# Feedback.net
KiCad netlist of a schematic drawn in Altium Designer
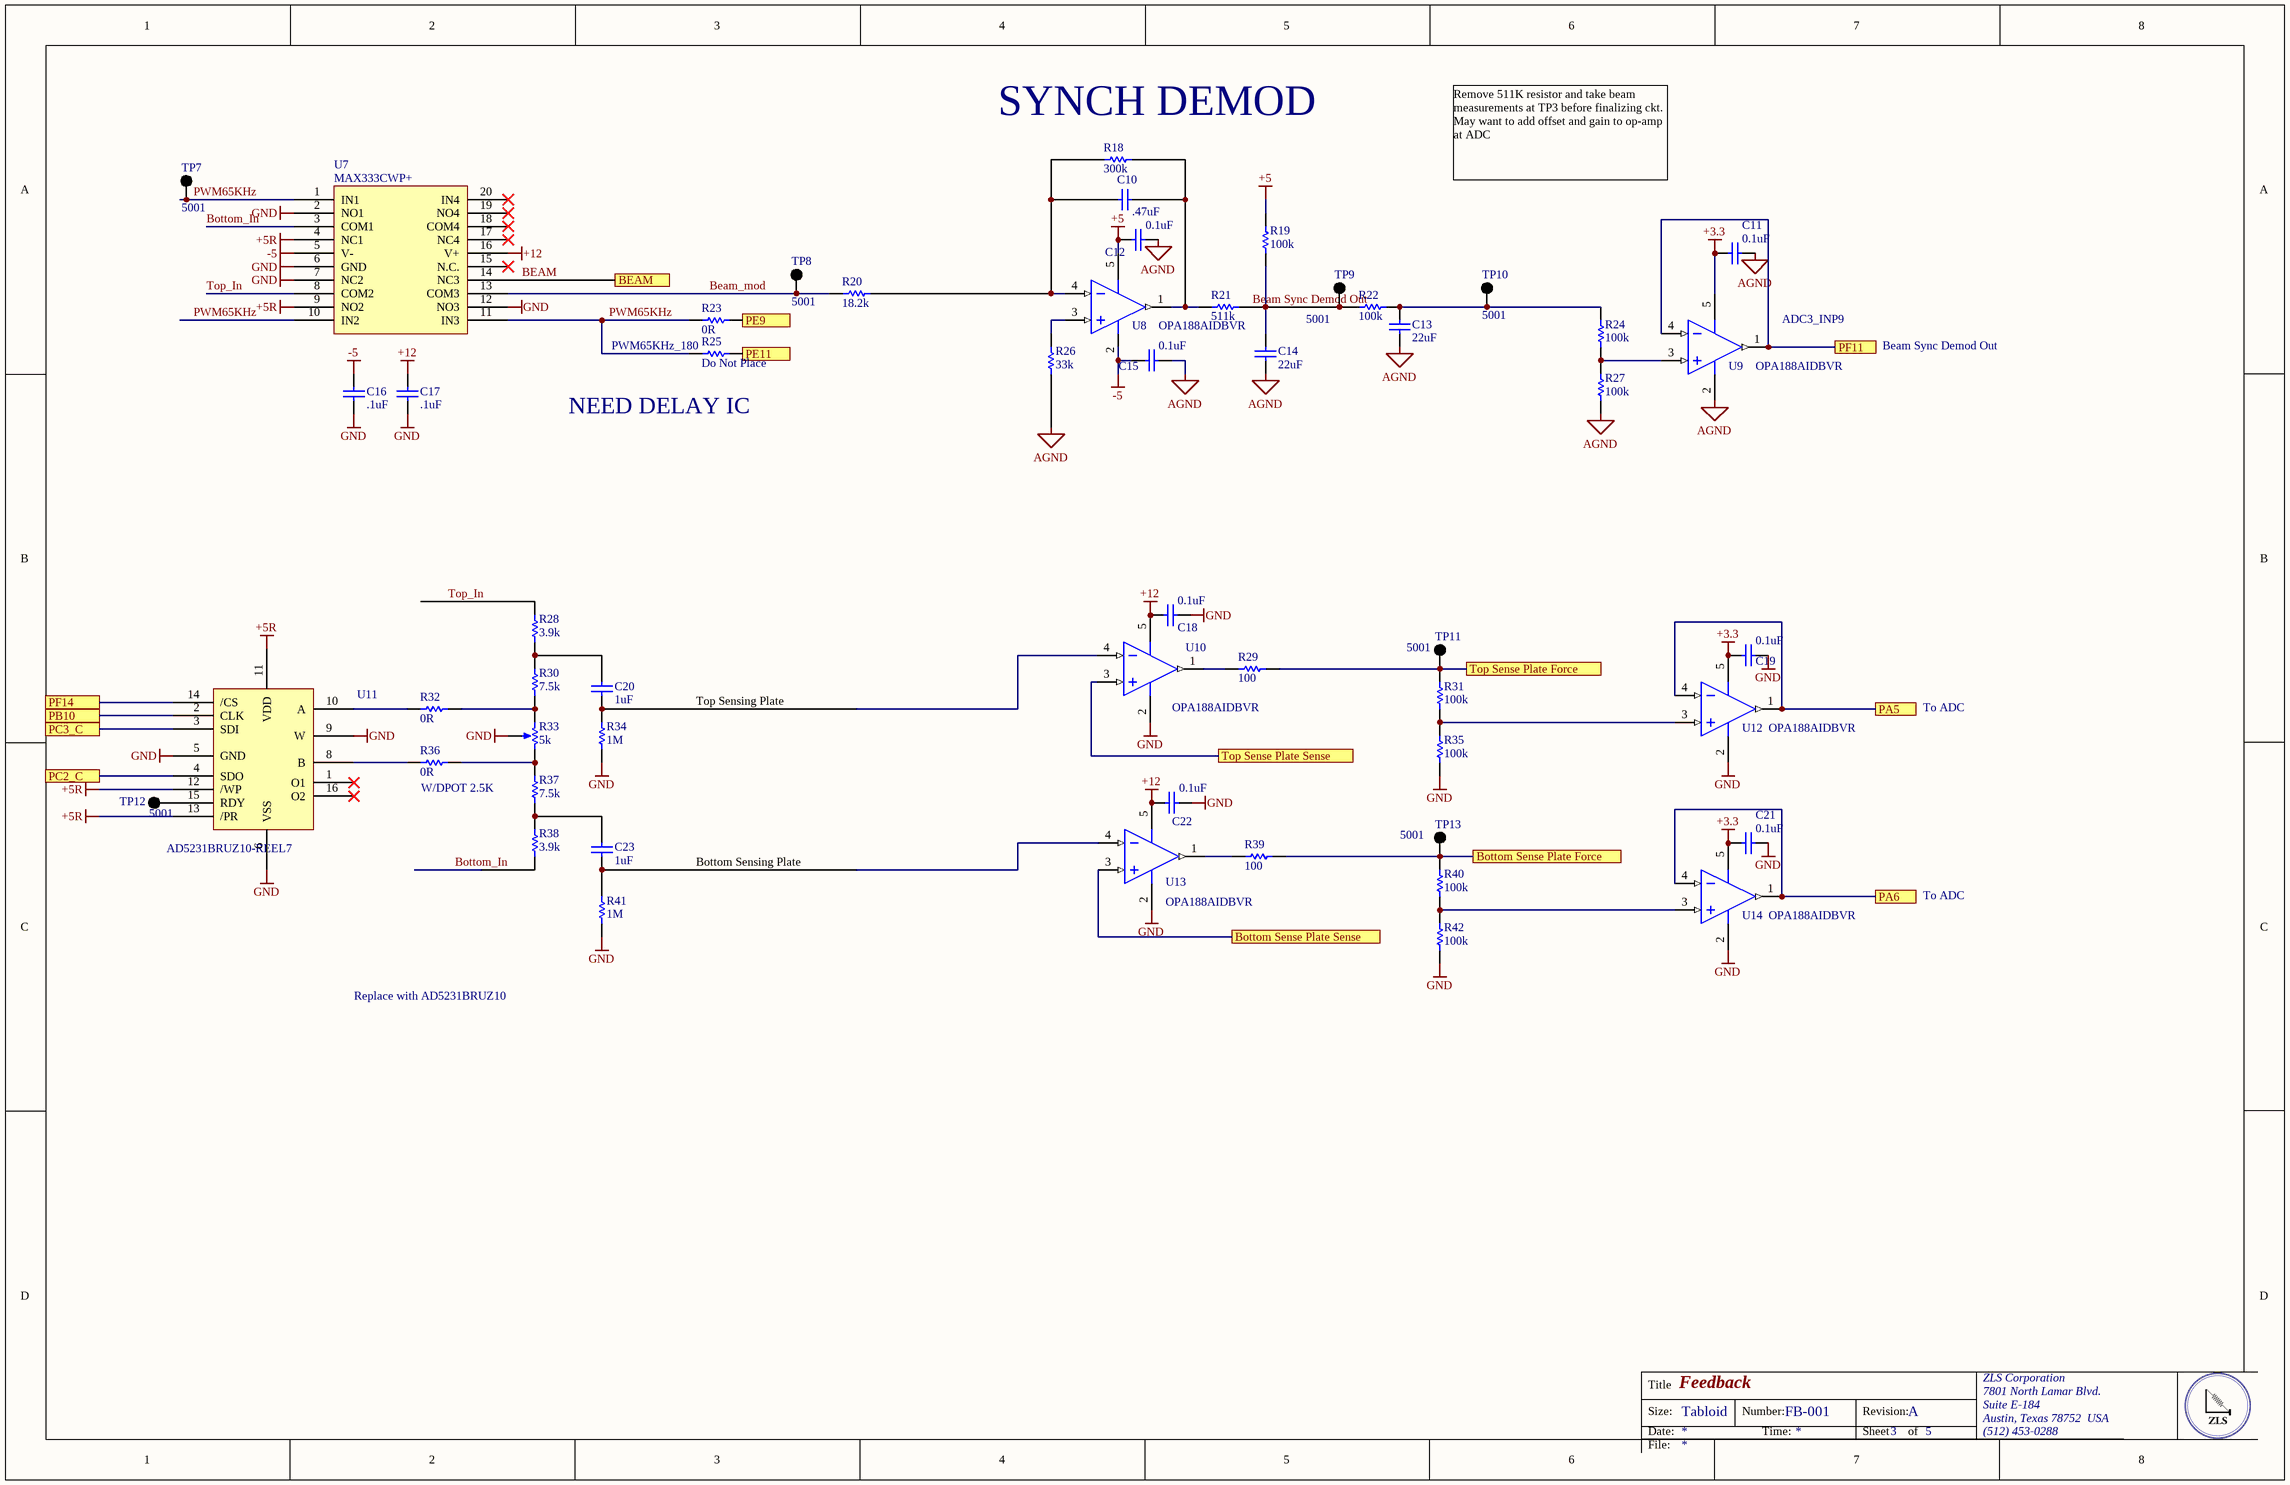
[diagram p0: Feedback.SchDoc]

(export (version "E")
  (design (tool "Eeschema 10.0.6"))
  (components
    (comp (ref "C10")
      (value ".47uF")
      (footprint "CAPC0805(2012)75_L")
      (description "0.47µF ±10% 16V Ceramic Capacitor X7R 0805 (2012 Metric)")
      (fields
        (field (name "MANUFACTURER") "Samsung")
        (field (name "MANUFACTURER PART NUMBER") "CL21B474KOFNNNE")
      )
      (libsource (lib "Altium Content Vault") (part "CMP-1036-02117-1"))
    )
    (comp (ref "C11")
      (value "0.1uF")
      (footprint "CAPC0402(1005)60_L")
      (description "CAP CER 0.1UF 10V X7R 0402")
      (fields
        (field (name "MANUFACTURER") "Murata Electronics North America")
        (field (name "MANUFACTURER PART NUMBER") "GRM155R71A104KA01D")
      )
      (libsource (lib "Altium Content Vault") (part "CMP-1034-00252-1"))
    )
    (comp (ref "C12")
      (value "0.1uF")
      (footprint "CAPC0402(1005)60_L")
      (description "CAP CER 0.1UF 10V X7R 0402")
      (fields
        (field (name "MANUFACTURER") "Murata Electronics North America")
        (field (name "MANUFACTURER PART NUMBER") "GRM155R71A104KA01D")
      )
      (libsource (lib "Altium Content Vault") (part "CMP-1034-00252-1"))
    )
    (comp (ref "C13")
      (value "22uF")
      (footprint "CAPC0805(2012)75_L")
      (description "22µF ±20% 16V Ceramic Capacitor X5R 0805 (2012 Metric)")
      (fields
        (field (name "MANUFACTURER") "Samsung")
        (field (name "MANUFACTURER PART NUMBER") "CL21A226MOCLRNC")
      )
      (libsource (lib "Altium Content Vault") (part "CMP-1036-02117-1"))
    )
    (comp (ref "C14")
      (value "22uF")
      (footprint "CAPC0805(2012)75_L")
      (description "22µF ±20% 16V Ceramic Capacitor X5R 0805 (2012 Metric)")
      (fields
        (field (name "MANUFACTURER") "Samsung")
        (field (name "MANUFACTURER PART NUMBER") "CL21A226MOCLRNC")
      )
      (libsource (lib "Altium Content Vault") (part "CMP-1036-02117-1"))
    )
    (comp (ref "C15")
      (value "0.1uF")
      (footprint "CAPC0402(1005)60_L")
      (description "CAP CER 0.1UF 10V X7R 0402")
      (fields
        (field (name "MANUFACTURER") "Murata Electronics North America")
        (field (name "MANUFACTURER PART NUMBER") "GRM155R71A104KA01D")
      )
      (libsource (lib "Altium Content Vault") (part "CMP-1034-00252-1"))
    )
    (comp (ref "C16")
      (value ".1uF")
      (footprint "CAPC0805(2012)75_M")
      (description "0.1µF ±10% 16V Ceramic Capacitor X7R 0805 (2012 Metric)")
      (fields
        (field (name "MANUFACTURER") "Yageo")
        (field (name "MANUFACTURER PART NUMBER") "CC0805KRX7R7BB104")
      )
      (libsource (lib "Altium Content Vault") (part "CMP-1036-01414-1"))
    )
    (comp (ref "C17")
      (value ".1uF")
      (footprint "CAPC0805(2012)75_M")
      (description "0.1µF ±10% 16V Ceramic Capacitor X7R 0805 (2012 Metric)")
      (fields
        (field (name "MANUFACTURER") "Yageo")
        (field (name "MANUFACTURER PART NUMBER") "CC0805KRX7R7BB104")
      )
      (libsource (lib "Altium Content Vault") (part "CMP-1036-01414-1"))
    )
    (comp (ref "C18")
      (value "0.1uF")
      (footprint "CAPC0402(1005)60_L")
      (description "CAP CER 0.1UF 10V X7R 0402")
      (fields
        (field (name "MANUFACTURER") "Murata Electronics North America")
        (field (name "MANUFACTURER PART NUMBER") "GRM155R71A104KA01D")
      )
      (libsource (lib "Altium Content Vault") (part "CMP-1034-00252-1"))
    )
    (comp (ref "C19")
      (value "0.1uF")
      (footprint "CAPC0402(1005)60_L")
      (description "CAP CER 0.1UF 10V X7R 0402")
      (fields
        (field (name "MANUFACTURER") "Murata Electronics North America")
        (field (name "MANUFACTURER PART NUMBER") "GRM155R71A104KA01D")
      )
      (libsource (lib "Altium Content Vault") (part "CMP-1034-00252-1"))
    )
    (comp (ref "C20")
      (value "1uF")
      (footprint "CAPC0402(1005)60_L")
      (description "1µF ±10% 16V Ceramic Capacitor X5R 0402 (1005 Metric)")
      (fields
        (field (name "MANUFACTURER") "Samsung")
        (field (name "MANUFACTURER PART NUMBER") "CL05A105KO5NNNC")
      )
      (libsource (lib "Altium Content Vault") (part "CMP-1034-00252-1"))
    )
    (comp (ref "C21")
      (value "0.1uF")
      (footprint "CAPC0402(1005)60_L")
      (description "CAP CER 0.1UF 10V X7R 0402")
      (fields
        (field (name "MANUFACTURER") "Murata Electronics North America")
        (field (name "MANUFACTURER PART NUMBER") "GRM155R71A104KA01D")
      )
      (libsource (lib "Altium Content Vault") (part "CMP-1034-00252-1"))
    )
    (comp (ref "C22")
      (value "0.1uF")
      (footprint "CAPC0402(1005)60_L")
      (description "CAP CER 0.1UF 10V X7R 0402")
      (fields
        (field (name "MANUFACTURER") "Murata Electronics North America")
        (field (name "MANUFACTURER PART NUMBER") "GRM155R71A104KA01D")
      )
      (libsource (lib "Altium Content Vault") (part "CMP-1034-00252-1"))
    )
    (comp (ref "C23")
      (value "1uF")
      (footprint "CAPC0402(1005)60_L")
      (description "1µF ±10% 16V Ceramic Capacitor X5R 0402 (1005 Metric)")
      (fields
        (field (name "MANUFACTURER") "Samsung")
        (field (name "MANUFACTURER PART NUMBER") "CL05A105KO5NNNC")
      )
      (libsource (lib "Altium Content Vault") (part "CMP-1034-00252-1"))
    )
    (comp (ref "R18")
      (value "300k")
      (footprint "RESC1005X40X25LL05T05")
      (description "RES SMD 300K OHM 1% 1/16W 0402")
      (fields (field (name "MANUFACTURER") "Vishay Dale") (field (name "PART NUMBER") "CRCW0402300KFKED"))
      (libsource (lib "Altium Content Vault") (part "RES"))
    )
    (comp (ref "R19")
      (value "100k")
      (footprint "RESC0402(1005)_M")
      (description "100k 0.063W 1% 0402 (1005 Metric)  SMD")
      (fields
        (field (name "MANUFACTURER") "Panasonic")
        (field (name "MANUFACTURER PART NUMBER") "ERJ-2RKF1003X")
      )
      (libsource (lib "Altium Content Vault") (part "RES"))
    )
    (comp (ref "R20")
      (value "18.2k")
      (footprint "RESC1005X40X25NL05T05")
      (description "RES SMD 18.2K OHM 1% 1/16W 0402")
      (fields (field (name "MANUFACTURER") "Vishay Dale") (field (name "PART NUMBER") "CRCW040218K2FKED"))
      (libsource (lib "Altium Content Vault") (part "RES"))
    )
    (comp (ref "R21")
      (value "511k")
      (footprint "RESC1005X40X25ML05T05")
      (description "RES SMD 511K OHM 1% 1/10W 0402")
      (fields (field (name "PART NUMBER") "ERJ-2RKF5113X") (field (name "MANUFACTURER") "Panasonic"))
      (libsource (lib "Altium Content Vault") (part "RES"))
    )
    (comp (ref "R22")
      (value "100k")
      (footprint "RESC0402(1005)_M")
      (description "100k 0.063W 1% 0402 (1005 Metric)  SMD")
      (fields
        (field (name "MANUFACTURER") "Panasonic")
        (field (name "MANUFACTURER PART NUMBER") "ERJ-2RKF1003X")
      )
      (libsource (lib "Altium Content Vault") (part "RES"))
    )
    (comp (ref "R23")
      (value "0R")
      (footprint "RESC1005X40X25NL05T10")
      (description "RES SMD 0 OHM JUMPER 1/16W 0402")
      (fields (field (name "MANUFACTURER") "Yageo / Phycomp") (field (name "PART NUMBER") "RC0402JR-070RL"))
      (libsource (lib "Altium Content Vault") (part "RES"))
    )
    (comp (ref "R24")
      (value "100k")
      (footprint "RESC0402(1005)_M")
      (description "100k 0.063W 1% 0402 (1005 Metric)  SMD")
      (fields
        (field (name "MANUFACTURER") "Panasonic")
        (field (name "MANUFACTURER PART NUMBER") "ERJ-2RKF1003X")
      )
      (libsource (lib "Altium Content Vault") (part "RES"))
    )
    (comp (ref "R25")
      (value "Do Not Place")
      (footprint "RESC1005X40X25NL05T10")
      (description "RES SMD 0 OHM JUMPER 1/16W 0402")
      (fields (field (name "MANUFACTURER") "Yageo / Phycomp") (field (name "PART NUMBER") "RC0402JR-070RL"))
      (libsource (lib "Altium Content Vault") (part "RES"))
    )
    (comp (ref "R26")
      (value "33k")
      (footprint "RESC0402(1005)_N")
      (description "RES SMD 33K OHM 1% 1/16W 0402")
      (fields (field (name "POWER") "0.063 W") (field (name "TOLERANCE") "1 %"))
      (libsource (lib "Altium Content Vault") (part "RES"))
    )
    (comp (ref "R27")
      (value "100k")
      (footprint "RESC0402(1005)_M")
      (description "100k 0.063W 1% 0402 (1005 Metric)  SMD")
      (fields
        (field (name "MANUFACTURER") "Panasonic")
        (field (name "MANUFACTURER PART NUMBER") "ERJ-2RKF1003X")
      )
      (libsource (lib "Altium Content Vault") (part "RES"))
    )
    (comp (ref "R28")
      (value "3.9k")
      (footprint "RESC1005X40X25NL05T05")
      (description "RES SMD 3.9K OHM 1% 1/16W 0402")
      (fields (field (name "MANUFACTURER") "Vishay Dale") (field (name "PART NUMBER") "CRCW04023K90FKED"))
      (libsource (lib "Altium Content Vault") (part "RES"))
    )
    (comp (ref "R29")
      (value "100")
      (footprint "RESC0402(1005)_N")
      (description "RES SMD 100 OHM 1% 1/16W 0402")
      (fields (field (name "TOLERANCE") "1 %") (field (name "POWER") "0.063 W"))
      (libsource (lib "Altium Content Vault") (part "RES"))
    )
    (comp (ref "R30")
      (value "7.5k")
      (footprint "RESC1005X40X25LL05T05")
      (description "RES SMD 7.5K OHM 1% 1/16W 0402")
      (fields (field (name "MANUFACTURER") "Vishay Dale") (field (name "PART NUMBER") "CRCW04027K50FKED"))
      (libsource (lib "Altium Content Vault") (part "RES"))
    )
    (comp (ref "R31")
      (value "100k")
      (footprint "RESC0402(1005)_M")
      (description "100k 0.063W 1% 0402 (1005 Metric)  SMD")
      (fields
        (field (name "MANUFACTURER") "Panasonic")
        (field (name "MANUFACTURER PART NUMBER") "ERJ-2RKF1003X")
      )
      (libsource (lib "Altium Content Vault") (part "RES"))
    )
    (comp (ref "R32")
      (value "0R")
      (footprint "RESC1005X40X25NL05T10")
      (description "RES SMD 0 OHM JUMPER 1/16W 0402")
      (fields (field (name "MANUFACTURER") "Yageo / Phycomp") (field (name "PART NUMBER") "RC0402JR-070RL"))
      (libsource (lib "Altium Content Vault") (part "RES"))
    )
    (comp (ref "R33")
      (value "Do Not Place")
      (footprint "Trimmer 2.54")
      (description "TRIMMER 5K OHM 0.25W PC PIN")
      (fields
        (field (name "MANUFACTURER") "Vishay Foil Resistors (Division of Vishay Precision Group)")
        (field (name "MANUFACTURER PART NUMBER") "Y00535K00000J0L")
        (field (name "RESISTANCE (OHMS)") "5k")
      )
      (libsource (lib "ZLS_Schematic_lib") (part "Trimmer"))
    )
    (comp (ref "R34")
      (value "1M")
      (footprint "RESC1005X40X25NL05T05")
      (description "RES SMD 1M OHM 1% 1/16W 0402")
      (fields (field (name "MANUFACTURER") "Vishay Dale") (field (name "PART NUMBER") "CRCW04021M00FKED"))
      (libsource (lib "Altium Content Vault") (part "RES"))
    )
    (comp (ref "R35")
      (value "100k")
      (footprint "RESC0402(1005)_M")
      (description "100k 0.063W 1% 0402 (1005 Metric)  SMD")
      (fields
        (field (name "MANUFACTURER") "Panasonic")
        (field (name "MANUFACTURER PART NUMBER") "ERJ-2RKF1003X")
      )
      (libsource (lib "Altium Content Vault") (part "RES"))
    )
    (comp (ref "R36")
      (value "0R")
      (footprint "RESC1005X40X25NL05T10")
      (description "RES SMD 0 OHM JUMPER 1/16W 0402")
      (fields (field (name "MANUFACTURER") "Yageo / Phycomp") (field (name "PART NUMBER") "RC0402JR-070RL"))
      (libsource (lib "Altium Content Vault") (part "RES"))
    )
    (comp (ref "R37")
      (value "7.5k")
      (footprint "RESC1005X40X25LL05T05")
      (description "RES SMD 7.5K OHM 1% 1/16W 0402")
      (fields (field (name "MANUFACTURER") "Vishay Dale") (field (name "PART NUMBER") "CRCW04027K50FKED"))
      (libsource (lib "Altium Content Vault") (part "RES"))
    )
    (comp (ref "R38")
      (value "3.9k")
      (footprint "RESC1005X40X25NL05T05")
      (description "RES SMD 3.9K OHM 1% 1/16W 0402")
      (fields (field (name "MANUFACTURER") "Vishay Dale") (field (name "PART NUMBER") "CRCW04023K90FKED"))
      (libsource (lib "Altium Content Vault") (part "RES"))
    )
    (comp (ref "R39")
      (value "100")
      (footprint "RESC0402(1005)_N")
      (description "RES SMD 100 OHM 1% 1/16W 0402")
      (fields (field (name "TOLERANCE") "1 %") (field (name "POWER") "0.063 W"))
      (libsource (lib "Altium Content Vault") (part "RES"))
    )
    (comp (ref "R40")
      (value "100k")
      (footprint "RESC0402(1005)_M")
      (description "100k 0.063W 1% 0402 (1005 Metric)  SMD")
      (fields
        (field (name "MANUFACTURER") "Panasonic")
        (field (name "MANUFACTURER PART NUMBER") "ERJ-2RKF1003X")
      )
      (libsource (lib "Altium Content Vault") (part "RES"))
    )
    (comp (ref "R41")
      (value "1M")
      (footprint "RESC1005X40X25NL05T05")
      (description "RES SMD 1M OHM 1% 1/16W 0402")
      (fields (field (name "MANUFACTURER") "Vishay Dale") (field (name "PART NUMBER") "CRCW04021M00FKED"))
      (libsource (lib "Altium Content Vault") (part "RES"))
    )
    (comp (ref "R42")
      (value "100k")
      (footprint "RESC0402(1005)_M")
      (description "100k 0.063W 1% 0402 (1005 Metric)  SMD")
      (fields
        (field (name "MANUFACTURER") "Panasonic")
        (field (name "MANUFACTURER PART NUMBER") "ERJ-2RKF1003X")
      )
      (libsource (lib "Altium Content Vault") (part "RES"))
    )
    (comp (ref "TP7")
      (value "5001")
      (footprint "KSTN-5001")
      (description "Test Point, Black, 1-Pin THD, RoHS, Bulk")
      (fields (field (name "MANUFACTURER") "Keystone"))
      (libsource (lib "Altium Content Vault") (part "KSTN-TP-5001"))
    )
    (comp (ref "TP8")
      (value "5001")
      (footprint "KSTN-5001")
      (description "Test Point, Black, 1-Pin THD, RoHS, Bulk")
      (fields (field (name "MANUFACTURER") "Keystone"))
      (libsource (lib "Altium Content Vault") (part "KSTN-TP-5001"))
    )
    (comp (ref "TP9")
      (value "5001")
      (footprint "KSTN-5001")
      (description "Test Point, Black, 1-Pin THD, RoHS, Bulk")
      (fields (field (name "MANUFACTURER") "Keystone"))
      (libsource (lib "Altium Content Vault") (part "KSTN-TP-5001"))
    )
    (comp (ref "TP10")
      (value "5001")
      (footprint "KSTN-5001")
      (description "Test Point, Black, 1-Pin THD, RoHS, Bulk")
      (fields (field (name "MANUFACTURER") "Keystone"))
      (libsource (lib "Altium Content Vault") (part "KSTN-TP-5001"))
    )
    (comp (ref "TP11")
      (value "5001")
      (footprint "KSTN-5001")
      (description "Test Point, Black, 1-Pin THD, RoHS, Bulk")
      (fields (field (name "MANUFACTURER") "Keystone"))
      (libsource (lib "Altium Content Vault") (part "KSTN-TP-5001"))
    )
    (comp (ref "TP12")
      (value "5001")
      (footprint "KSTN-5001")
      (description "Test Point, Black, 1-Pin THD, RoHS, Bulk")
      (fields (field (name "MANUFACTURER") "Keystone"))
      (libsource (lib "Altium Content Vault") (part "KSTN-TP-5001"))
    )
    (comp (ref "TP13")
      (value "5001")
      (footprint "KSTN-5001")
      (description "Test Point, Black, 1-Pin THD, RoHS, Bulk")
      (fields (field (name "MANUFACTURER") "Keystone"))
      (libsource (lib "Altium Content Vault") (part "KSTN-TP-5001"))
    )
    (comp (ref "U7")
      (value "MAX333CWP+")
      (footprint "TSOP65P640X90-20N")
      (description "IC SWITCH QUAD SPDT 20TSSOP")
      (fields (field (name "MANUFACTURER") "Maxim") (field (name "MANUFACTURER PART NUMBER") "MAX333AEUP+"))
      (libsource (lib "ZLS_Schematic_lib") (part "MAX333CWP+"))
    )
    (comp (ref "U8")
      (value "OPA188AIDBVR")
      (footprint "DBV0005A_M")
      (fields (field (name "MANUFACTURER") "Texas Instruments"))
      (libsource (lib "Altium Content Vault") (part "CMP-0809-00005-2"))
    )
    (comp (ref "U9")
      (value "OPA188AIDBVR")
      (footprint "DBV0005A_M")
      (fields (field (name "MANUFACTURER") "Texas Instruments"))
      (libsource (lib "Altium Content Vault") (part "CMP-0809-00005-2"))
    )
    (comp (ref "U10")
      (value "OPA188AIDBVR")
      (footprint "DBV0005A_M")
      (fields (field (name "MANUFACTURER") "Texas Instruments"))
      (libsource (lib "Altium Content Vault") (part "CMP-0809-00005-2"))
    )
    (comp (ref "U11")
      (value "AD5231BRUZ10-REEL7")
      (footprint "AD5231BRUZ10")
      (description "Digital Potentiometer 1024POS 10KOhm Single 16-Pin TSSOP T/R")
      (fields (field (name "MANUFACTURER") "Analog Devices") (field (name "TOLERANCE") "20%"))
      (libsource (lib "ZLS_Schematic_lib") (part "AD5231BRUZ10"))
    )
    (comp (ref "U12")
      (value "OPA188AIDBVR")
      (footprint "DBV0005A_M")
      (fields (field (name "MANUFACTURER") "Texas Instruments"))
      (libsource (lib "Altium Content Vault") (part "CMP-0809-00005-2"))
    )
    (comp (ref "U13")
      (value "OPA188AIDBVR")
      (footprint "DBV0005A_M")
      (fields (field (name "MANUFACTURER") "Texas Instruments"))
      (libsource (lib "Altium Content Vault") (part "CMP-0809-00005-2"))
    )
    (comp (ref "U14")
      (value "OPA188AIDBVR")
      (footprint "DBV0005A_M")
      (fields (field (name "MANUFACTURER") "Texas Instruments"))
      (libsource (lib "Altium Content Vault") (part "CMP-0809-00005-2"))
    )
  )
  (nets
    (net (code "1") (name "+3.3") (class "Default")
      (node (ref "C11") (pin "2") (pinfunction "2_2") (pintype "passive"))
      (node (ref "C19") (pin "2") (pinfunction "2_2") (pintype "passive"))
      (node (ref "C21") (pin "2") (pinfunction "2_2") (pintype "passive"))
      (node (ref "U12") (pin "5") (pinfunction "V+_5") (pintype "power_in"))
      (node (ref "U14") (pin "5") (pinfunction "V+_5") (pintype "power_in"))
      (node (ref "U9") (pin "5") (pinfunction "V+_5") (pintype "power_in"))
    )
    (net (code "2") (name "+5") (class "Default")
      (node (ref "C12") (pin "2") (pinfunction "2_2") (pintype "passive"))
      (node (ref "R19") (pin "2") (pinfunction "2_2") (pintype "passive"))
      (node (ref "U8") (pin "5") (pinfunction "V+_5") (pintype "power_in"))
    )
    (net (code "3") (name "+5R") (class "Default")
      (node (ref "U11") (pin "11") (pinfunction "VDD_11") (pintype "passive"))
      (node (ref "U11") (pin "12") (pinfunction "/WP_12") (pintype "passive"))
      (node (ref "U11") (pin "13") (pinfunction "/PR_13") (pintype "passive"))
      (node (ref "U7") (pin "4") (pinfunction "NC1_4") (pintype "passive"))
      (node (ref "U7") (pin "9") (pinfunction "NO2_9") (pintype "passive"))
    )
    (net (code "4") (name "+12") (class "Default")
      (node (ref "C17") (pin "2") (pinfunction "2_2") (pintype "passive"))
      (node (ref "C18") (pin "2") (pinfunction "2_2") (pintype "passive"))
      (node (ref "C22") (pin "2") (pinfunction "2_2") (pintype "passive"))
      (node (ref "U10") (pin "5") (pinfunction "V+_5") (pintype "power_in"))
      (node (ref "U13") (pin "5") (pinfunction "V+_5") (pintype "power_in"))
      (node (ref "U7") (pin "16") (pinfunction "V+_16") (pintype "power_in"))
    )
    (net (code "5") (name "-5") (class "Default")
      (node (ref "C15") (pin "2") (pinfunction "2_2") (pintype "passive"))
      (node (ref "C16") (pin "2") (pinfunction "2_2") (pintype "passive"))
      (node (ref "U7") (pin "5") (pinfunction "V-_5") (pintype "power_in"))
      (node (ref "U8") (pin "2") (pinfunction "V-_2") (pintype "power_in"))
    )
    (net (code "6") (name "/BEAM") (class "Default")
      (node (ref "U7") (pin "14") (pinfunction "NC3_14") (pintype "passive"))
    )
    (net (code "7") (name "/Beam Sync Demod Out") (class "Default")
      (node (ref "C14") (pin "2") (pinfunction "2_2") (pintype "passive"))
      (node (ref "R19") (pin "1") (pinfunction "1_1") (pintype "passive"))
      (node (ref "R21") (pin "2") (pinfunction "2_2") (pintype "passive"))
      (node (ref "R22") (pin "2") (pinfunction "2_2") (pintype "passive"))
      (node (ref "TP9") (pin "1") (pintype "passive"))
    )
    (net (code "8") (name "/Beam_mod") (class "Default")
      (node (ref "R20") (pin "1") (pinfunction "1_1") (pintype "passive"))
      (node (ref "TP8") (pin "1") (pintype "passive"))
      (node (ref "U7") (pin "13") (pinfunction "COM3_13") (pintype "passive"))
    )
    (net (code "9") (name "/Bottom Sense Plate Force") (class "Default")
      (node (ref "R39") (pin "2") (pinfunction "2_2") (pintype "passive"))
      (node (ref "R40") (pin "2") (pinfunction "2_2") (pintype "passive"))
      (node (ref "TP13") (pin "1") (pintype "passive"))
    )
    (net (code "10") (name "/Bottom Sense Plate Sense") (class "Default")
      (node (ref "U13") (pin "3") (pinfunction "IN+_3") (pintype "input"))
    )
    (net (code "11") (name "/Bottom_In") (class "Default")
      (node (ref "R38") (pin "1") (pinfunction "1_1") (pintype "passive"))
      (node (ref "U7") (pin "3") (pinfunction "COM1_3") (pintype "passive"))
    )
    (net (code "12") (name "/PA5") (class "Default")
      (node (ref "U12") (pin "1") (pinfunction "OUT_1") (pintype "output"))
      (node (ref "U12") (pin "4") (pinfunction "IN-_4") (pintype "input"))
    )
    (net (code "13") (name "/PA6") (class "Default")
      (node (ref "U14") (pin "1") (pinfunction "OUT_1") (pintype "output"))
      (node (ref "U14") (pin "4") (pinfunction "IN-_4") (pintype "input"))
    )
    (net (code "14") (name "/PB10") (class "Default")
      (node (ref "U11") (pin "2") (pinfunction "CLK_2") (pintype "passive"))
    )
    (net (code "15") (name "/PC2_C") (class "Default")
      (node (ref "U11") (pin "4") (pinfunction "SDO_4") (pintype "passive"))
    )
    (net (code "16") (name "/PC3_C") (class "Default")
      (node (ref "U11") (pin "3") (pinfunction "SDI_3") (pintype "passive"))
    )
    (net (code "17") (name "/PE9") (class "Default")
      (node (ref "R23") (pin "2") (pinfunction "2_2") (pintype "passive"))
    )
    (net (code "18") (name "/PE11") (class "Default")
      (node (ref "R25") (pin "2") (pinfunction "2_2") (pintype "passive"))
    )
    (net (code "19") (name "/PF11") (class "Default")
      (node (ref "U9") (pin "1") (pinfunction "OUT_1") (pintype "output"))
      (node (ref "U9") (pin "4") (pinfunction "IN-_4") (pintype "input"))
    )
    (net (code "20") (name "/PF14") (class "Default")
      (node (ref "U11") (pin "14") (pinfunction "/CS_14") (pintype "passive"))
    )
    (net (code "21") (name "/PWM65KHz") (class "Default")
      (node (ref "R23") (pin "1") (pinfunction "1_1") (pintype "passive"))
      (node (ref "R25") (pin "1") (pinfunction "1_1") (pintype "passive"))
      (node (ref "TP7") (pin "1") (pintype "passive"))
      (node (ref "U7") (pin "1") (pinfunction "IN1_1") (pintype "passive"))
      (node (ref "U7") (pin "10") (pinfunction "IN2_10") (pintype "passive"))
      (node (ref "U7") (pin "11") (pinfunction "IN3_11") (pintype "passive"))
    )
    (net (code "22") (name "/Top Sense Plate Force") (class "Default")
      (node (ref "R29") (pin "2") (pinfunction "2_2") (pintype "passive"))
      (node (ref "R31") (pin "2") (pinfunction "2_2") (pintype "passive"))
      (node (ref "TP11") (pin "1") (pintype "passive"))
    )
    (net (code "23") (name "/Top Sense Plate Sense") (class "Default")
      (node (ref "U10") (pin "3") (pinfunction "IN+_3") (pintype "input"))
    )
    (net (code "24") (name "/Top_In") (class "Default")
      (node (ref "R28") (pin "2") (pinfunction "2_2") (pintype "passive"))
      (node (ref "U7") (pin "8") (pinfunction "COM2_8") (pintype "passive"))
    )
    (net (code "25") (name "AGND") (class "Default")
      (node (ref "C11") (pin "1") (pinfunction "1_1") (pintype "passive"))
      (node (ref "C12") (pin "1") (pinfunction "1_1") (pintype "passive"))
      (node (ref "C13") (pin "1") (pinfunction "1_1") (pintype "passive"))
      (node (ref "C14") (pin "1") (pinfunction "1_1") (pintype "passive"))
      (node (ref "C15") (pin "1") (pinfunction "1_1") (pintype "passive"))
      (node (ref "R26") (pin "1") (pinfunction "1_1") (pintype "passive"))
      (node (ref "R27") (pin "1") (pinfunction "1_1") (pintype "passive"))
      (node (ref "U9") (pin "2") (pinfunction "V-_2") (pintype "power_in"))
    )
    (net (code "26") (name "GND") (class "Default")
      (node (ref "C16") (pin "1") (pinfunction "1_1") (pintype "passive"))
      (node (ref "C17") (pin "1") (pinfunction "1_1") (pintype "passive"))
      (node (ref "C18") (pin "1") (pinfunction "1_1") (pintype "passive"))
      (node (ref "C19") (pin "1") (pinfunction "1_1") (pintype "passive"))
      (node (ref "C21") (pin "1") (pinfunction "1_1") (pintype "passive"))
      (node (ref "C22") (pin "1") (pinfunction "1_1") (pintype "passive"))
      (node (ref "R33") (pin "2") (pinfunction "b_2") (pintype "passive"))
      (node (ref "R34") (pin "1") (pinfunction "1_1") (pintype "passive"))
      (node (ref "R35") (pin "1") (pinfunction "1_1") (pintype "passive"))
      (node (ref "R41") (pin "1") (pinfunction "1_1") (pintype "passive"))
      (node (ref "R42") (pin "1") (pinfunction "1_1") (pintype "passive"))
      (node (ref "U10") (pin "2") (pinfunction "V-_2") (pintype "power_in"))
      (node (ref "U11") (pin "5") (pinfunction "GND_5") (pintype "passive"))
      (node (ref "U11") (pin "6") (pinfunction "VSS_6") (pintype "passive"))
      (node (ref "U11") (pin "9") (pinfunction "W_9") (pintype "passive"))
      (node (ref "U12") (pin "2") (pinfunction "V-_2") (pintype "power_in"))
      (node (ref "U13") (pin "2") (pinfunction "V-_2") (pintype "power_in"))
      (node (ref "U14") (pin "2") (pinfunction "V-_2") (pintype "power_in"))
      (node (ref "U7") (pin "12") (pinfunction "NO3_12") (pintype "passive"))
      (node (ref "U7") (pin "2") (pinfunction "NO1_2") (pintype "passive"))
      (node (ref "U7") (pin "6") (pinfunction "GND_6") (pintype "passive"))
      (node (ref "U7") (pin "7") (pinfunction "NC2_7") (pintype "passive"))
    )
    (net (code "27") (name "Net-(C13-Pad2)") (class "Default")
      (node (ref "C13") (pin "2") (pinfunction "2_2") (pintype "passive"))
      (node (ref "R22") (pin "1") (pinfunction "1_1") (pintype "passive"))
      (node (ref "R24") (pin "2") (pinfunction "2_2") (pintype "passive"))
      (node (ref "TP10") (pin "1") (pintype "passive"))
    )
    (net (code "28") (name "Net-(C20-Pad2)") (class "Default")
      (node (ref "C20") (pin "2") (pinfunction "2_2") (pintype "passive"))
      (node (ref "R28") (pin "1") (pinfunction "1_1") (pintype "passive"))
      (node (ref "R30") (pin "2") (pinfunction "2_2") (pintype "passive"))
    )
    (net (code "29") (name "Net-(C23-Pad2)") (class "Default")
      (node (ref "C23") (pin "2") (pinfunction "2_2") (pintype "passive"))
      (node (ref "R37") (pin "1") (pinfunction "1_1") (pintype "passive"))
      (node (ref "R38") (pin "2") (pinfunction "2_2") (pintype "passive"))
    )
    (net (code "30") (name "Net-(R33-a)") (class "Default")
      (node (ref "R30") (pin "1") (pinfunction "1_1") (pintype "passive"))
      (node (ref "R32") (pin "2") (pinfunction "2_2") (pintype "passive"))
      (node (ref "R33") (pin "1") (pinfunction "a_1") (pintype "passive"))
    )
    (net (code "31") (name "Net-(R33-c)") (class "Default")
      (node (ref "R33") (pin "3") (pinfunction "c_3") (pintype "passive"))
      (node (ref "R36") (pin "2") (pinfunction "2_2") (pintype "passive"))
      (node (ref "R37") (pin "2") (pinfunction "2_2") (pintype "passive"))
    )
    (net (code "32") (name "Net-(U8-IN+)") (class "Default")
      (node (ref "R26") (pin "2") (pinfunction "2_2") (pintype "passive"))
      (node (ref "U8") (pin "3") (pinfunction "IN+_3") (pintype "input"))
    )
    (net (code "33") (name "Net-(U8-IN-)") (class "Default")
      (node (ref "C10") (pin "1") (pinfunction "1_1") (pintype "passive"))
      (node (ref "R18") (pin "1") (pinfunction "1_1") (pintype "passive"))
      (node (ref "R20") (pin "2") (pinfunction "2_2") (pintype "passive"))
      (node (ref "U8") (pin "4") (pinfunction "IN-_4") (pintype "input"))
    )
    (net (code "34") (name "Net-(U8-OUT)") (class "Default")
      (node (ref "C10") (pin "2") (pinfunction "2_2") (pintype "passive"))
      (node (ref "R18") (pin "2") (pinfunction "2_2") (pintype "passive"))
      (node (ref "R21") (pin "1") (pinfunction "1_1") (pintype "passive"))
      (node (ref "U8") (pin "1") (pinfunction "OUT_1") (pintype "output"))
    )
    (net (code "35") (name "Net-(U9-IN+)") (class "Default")
      (node (ref "R24") (pin "1") (pinfunction "1_1") (pintype "passive"))
      (node (ref "R27") (pin "2") (pinfunction "2_2") (pintype "passive"))
      (node (ref "U9") (pin "3") (pinfunction "IN+_3") (pintype "input"))
    )
    (net (code "36") (name "Net-(U10-IN-)") (class "Default")
      (node (ref "C20") (pin "1") (pinfunction "1_1") (pintype "passive"))
      (node (ref "R34") (pin "2") (pinfunction "2_2") (pintype "passive"))
      (node (ref "U10") (pin "4") (pinfunction "IN-_4") (pintype "input"))
    )
    (net (code "37") (name "Net-(U10-OUT)") (class "Default")
      (node (ref "R29") (pin "1") (pinfunction "1_1") (pintype "passive"))
      (node (ref "U10") (pin "1") (pinfunction "OUT_1") (pintype "output"))
    )
    (net (code "38") (name "Net-(U11-A)") (class "Default")
      (node (ref "R32") (pin "1") (pinfunction "1_1") (pintype "passive"))
      (node (ref "U11") (pin "10") (pinfunction "A_10") (pintype "passive"))
    )
    (net (code "39") (name "Net-(U11-B)") (class "Default")
      (node (ref "R36") (pin "1") (pinfunction "1_1") (pintype "passive"))
      (node (ref "U11") (pin "8") (pinfunction "B_8") (pintype "passive"))
    )
    (net (code "40") (name "Net-(U11-RDY)") (class "Default")
      (node (ref "TP12") (pin "1") (pintype "passive"))
      (node (ref "U11") (pin "15") (pinfunction "RDY_15") (pintype "passive"))
    )
    (net (code "41") (name "Net-(U12-IN+)") (class "Default")
      (node (ref "R31") (pin "1") (pinfunction "1_1") (pintype "passive"))
      (node (ref "R35") (pin "2") (pinfunction "2_2") (pintype "passive"))
      (node (ref "U12") (pin "3") (pinfunction "IN+_3") (pintype "input"))
    )
    (net (code "42") (name "Net-(U13-IN-)") (class "Default")
      (node (ref "C23") (pin "1") (pinfunction "1_1") (pintype "passive"))
      (node (ref "R41") (pin "2") (pinfunction "2_2") (pintype "passive"))
      (node (ref "U13") (pin "4") (pinfunction "IN-_4") (pintype "input"))
    )
    (net (code "43") (name "Net-(U13-OUT)") (class "Default")
      (node (ref "R39") (pin "1") (pinfunction "1_1") (pintype "passive"))
      (node (ref "U13") (pin "1") (pinfunction "OUT_1") (pintype "output"))
    )
    (net (code "44") (name "Net-(U14-IN+)") (class "Default")
      (node (ref "R40") (pin "1") (pinfunction "1_1") (pintype "passive"))
      (node (ref "R42") (pin "2") (pinfunction "2_2") (pintype "passive"))
      (node (ref "U14") (pin "3") (pinfunction "IN+_3") (pintype "input"))
    )
    (net (code "45") (name "unconnected-(U7-COM4-Pad18)") (class "Default")
      (node (ref "U7") (pin "18") (pinfunction "COM4_18") (pintype "passive+no_connect"))
    )
    (net (code "46") (name "unconnected-(U7-IN4-Pad20)") (class "Default")
      (node (ref "U7") (pin "20") (pinfunction "IN4_20") (pintype "passive+no_connect"))
    )
    (net (code "47") (name "unconnected-(U7-N.C.-Pad15)") (class "Default")
      (node (ref "U7") (pin "15") (pinfunction "N.C._15") (pintype "passive+no_connect"))
    )
    (net (code "48") (name "unconnected-(U7-NC4-Pad17)") (class "Default")
      (node (ref "U7") (pin "17") (pinfunction "NC4_17") (pintype "passive+no_connect"))
    )
    (net (code "49") (name "unconnected-(U7-NO4-Pad19)") (class "Default")
      (node (ref "U7") (pin "19") (pinfunction "NO4_19") (pintype "passive+no_connect"))
    )
    (net (code "50") (name "unconnected-(U11-O1-Pad1)") (class "Default")
      (node (ref "U11") (pin "1") (pinfunction "O1_1") (pintype "passive+no_connect"))
    )
    (net (code "51") (name "unconnected-(U11-O2-Pad16)") (class "Default")
      (node (ref "U11") (pin "16") (pinfunction "O2_16") (pintype "passive+no_connect"))
    )
  )
)
